# LinePCB_Schematic_ETCautoPrikratki.net
KiCad netlist of a schematic drawn in EasyEDA
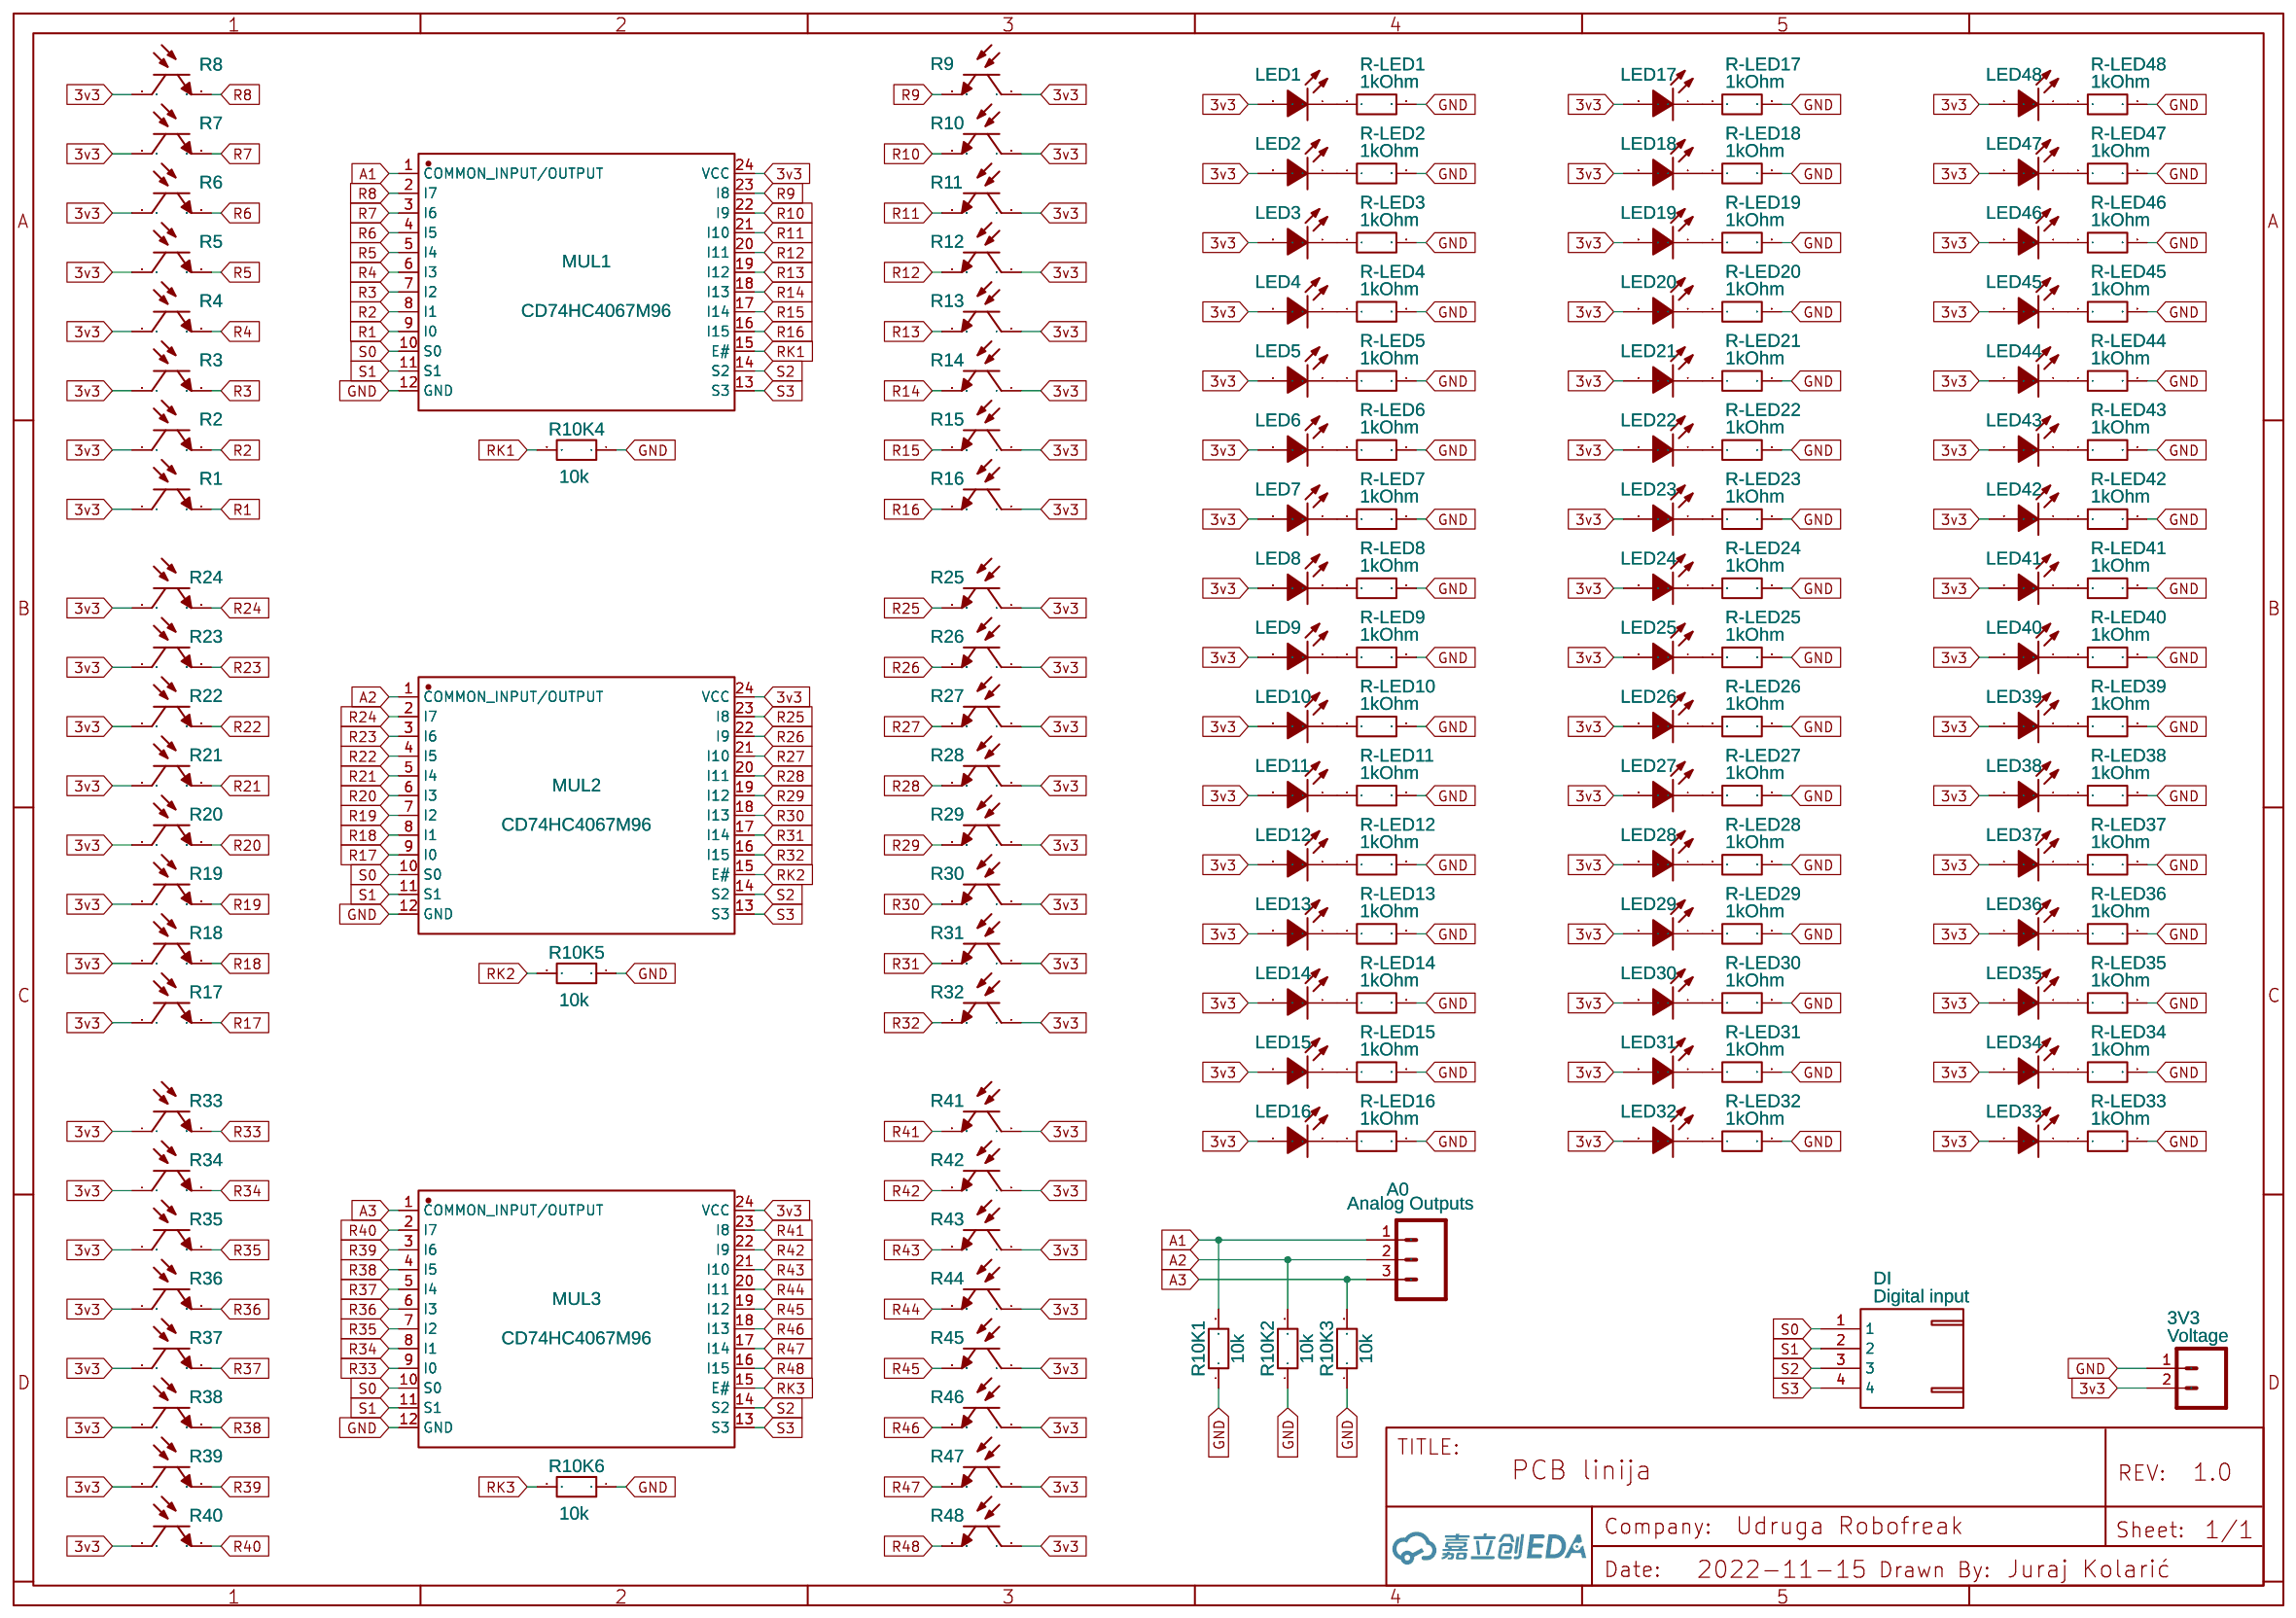
[diagram p0: schematic sheet]

(export (version "E")
  (design (tool "Eeschema 10.0.6"))
  (components
    (comp (ref "3V3") (value "Voltage") (libsource (lib "") (part "JST-XH-1X02-2.50MM-THM JS")))
    (comp (ref "A0") (value "Analog Outputs") (libsource (lib "") (part "JST-XH-1X03-2.50MM-THM JS")))
    (comp (ref "DI") (value "Digital input") (libsource (lib "") (part "JST-XH-4-Pin")))
    (comp (ref "LED1")
      (value "3528 Red LED")
      (fields (field (name "Manufacturer Part") "XL-3528SURC") (field (name "Manufacturer") "XINGLIGHT(成兴光)"))
      (libsource (lib "") (part "3528 Red LED"))
    )
    (comp (ref "LED2")
      (value "3528 Red LED")
      (fields (field (name "Manufacturer Part") "XL-3528SURC") (field (name "Manufacturer") "XINGLIGHT(成兴光)"))
      (libsource (lib "") (part "3528 Red LED"))
    )
    (comp (ref "LED3")
      (value "3528 Red LED")
      (fields (field (name "Manufacturer Part") "XL-3528SURC") (field (name "Manufacturer") "XINGLIGHT(成兴光)"))
      (libsource (lib "") (part "3528 Red LED"))
    )
    (comp (ref "LED4")
      (value "3528 Red LED")
      (fields (field (name "Manufacturer Part") "XL-3528SURC") (field (name "Manufacturer") "XINGLIGHT(成兴光)"))
      (libsource (lib "") (part "3528 Red LED"))
    )
    (comp (ref "LED5")
      (value "3528 Red LED")
      (fields (field (name "Manufacturer Part") "XL-3528SURC") (field (name "Manufacturer") "XINGLIGHT(成兴光)"))
      (libsource (lib "") (part "3528 Red LED"))
    )
    (comp (ref "LED6")
      (value "3528 Red LED")
      (fields (field (name "Manufacturer Part") "XL-3528SURC") (field (name "Manufacturer") "XINGLIGHT(成兴光)"))
      (libsource (lib "") (part "3528 Red LED"))
    )
    (comp (ref "LED7")
      (value "3528 Red LED")
      (fields (field (name "Manufacturer Part") "XL-3528SURC") (field (name "Manufacturer") "XINGLIGHT(成兴光)"))
      (libsource (lib "") (part "3528 Red LED"))
    )
    (comp (ref "LED8")
      (value "3528 Red LED")
      (fields (field (name "Manufacturer Part") "XL-3528SURC") (field (name "Manufacturer") "XINGLIGHT(成兴光)"))
      (libsource (lib "") (part "3528 Red LED"))
    )
    (comp (ref "LED9")
      (value "3528 Red LED")
      (fields (field (name "Manufacturer Part") "XL-3528SURC") (field (name "Manufacturer") "XINGLIGHT(成兴光)"))
      (libsource (lib "") (part "3528 Red LED"))
    )
    (comp (ref "LED10")
      (value "3528 Red LED")
      (fields (field (name "Manufacturer Part") "XL-3528SURC") (field (name "Manufacturer") "XINGLIGHT(成兴光)"))
      (libsource (lib "") (part "3528 Red LED"))
    )
    (comp (ref "LED11")
      (value "3528 Red LED")
      (fields (field (name "Manufacturer Part") "XL-3528SURC") (field (name "Manufacturer") "XINGLIGHT(成兴光)"))
      (libsource (lib "") (part "3528 Red LED"))
    )
    (comp (ref "LED12")
      (value "3528 Red LED")
      (fields (field (name "Manufacturer Part") "XL-3528SURC") (field (name "Manufacturer") "XINGLIGHT(成兴光)"))
      (libsource (lib "") (part "3528 Red LED"))
    )
    (comp (ref "LED13")
      (value "3528 Red LED")
      (fields (field (name "Manufacturer Part") "XL-3528SURC") (field (name "Manufacturer") "XINGLIGHT(成兴光)"))
      (libsource (lib "") (part "3528 Red LED"))
    )
    (comp (ref "LED14")
      (value "3528 Red LED")
      (fields (field (name "Manufacturer Part") "XL-3528SURC") (field (name "Manufacturer") "XINGLIGHT(成兴光)"))
      (libsource (lib "") (part "3528 Red LED"))
    )
    (comp (ref "LED15")
      (value "3528 Red LED")
      (fields (field (name "Manufacturer Part") "XL-3528SURC") (field (name "Manufacturer") "XINGLIGHT(成兴光)"))
      (libsource (lib "") (part "3528 Red LED"))
    )
    (comp (ref "LED16")
      (value "3528 Red LED")
      (fields (field (name "Manufacturer Part") "XL-3528SURC") (field (name "Manufacturer") "XINGLIGHT(成兴光)"))
      (libsource (lib "") (part "3528 Red LED"))
    )
    (comp (ref "LED17")
      (value "3528 Red LED")
      (fields (field (name "Manufacturer Part") "XL-3528SURC") (field (name "Manufacturer") "XINGLIGHT(成兴光)"))
      (libsource (lib "") (part "3528 Red LED"))
    )
    (comp (ref "LED18")
      (value "3528 Red LED")
      (fields (field (name "Manufacturer Part") "XL-3528SURC") (field (name "Manufacturer") "XINGLIGHT(成兴光)"))
      (libsource (lib "") (part "3528 Red LED"))
    )
    (comp (ref "LED19")
      (value "3528 Red LED")
      (fields (field (name "Manufacturer Part") "XL-3528SURC") (field (name "Manufacturer") "XINGLIGHT(成兴光)"))
      (libsource (lib "") (part "3528 Red LED"))
    )
    (comp (ref "LED20")
      (value "3528 Red LED")
      (fields (field (name "Manufacturer Part") "XL-3528SURC") (field (name "Manufacturer") "XINGLIGHT(成兴光)"))
      (libsource (lib "") (part "3528 Red LED"))
    )
    (comp (ref "LED21")
      (value "3528 Red LED")
      (fields (field (name "Manufacturer Part") "XL-3528SURC") (field (name "Manufacturer") "XINGLIGHT(成兴光)"))
      (libsource (lib "") (part "3528 Red LED"))
    )
    (comp (ref "LED22")
      (value "3528 Red LED")
      (fields (field (name "Manufacturer Part") "XL-3528SURC") (field (name "Manufacturer") "XINGLIGHT(成兴光)"))
      (libsource (lib "") (part "3528 Red LED"))
    )
    (comp (ref "LED23")
      (value "3528 Red LED")
      (fields (field (name "Manufacturer Part") "XL-3528SURC") (field (name "Manufacturer") "XINGLIGHT(成兴光)"))
      (libsource (lib "") (part "3528 Red LED"))
    )
    (comp (ref "LED24")
      (value "3528 Red LED")
      (fields (field (name "Manufacturer Part") "XL-3528SURC") (field (name "Manufacturer") "XINGLIGHT(成兴光)"))
      (libsource (lib "") (part "3528 Red LED"))
    )
    (comp (ref "LED25")
      (value "3528 Red LED")
      (fields (field (name "Manufacturer Part") "XL-3528SURC") (field (name "Manufacturer") "XINGLIGHT(成兴光)"))
      (libsource (lib "") (part "3528 Red LED"))
    )
    (comp (ref "LED26")
      (value "3528 Red LED")
      (fields (field (name "Manufacturer Part") "XL-3528SURC") (field (name "Manufacturer") "XINGLIGHT(成兴光)"))
      (libsource (lib "") (part "3528 Red LED"))
    )
    (comp (ref "LED27")
      (value "3528 Red LED")
      (fields (field (name "Manufacturer Part") "XL-3528SURC") (field (name "Manufacturer") "XINGLIGHT(成兴光)"))
      (libsource (lib "") (part "3528 Red LED"))
    )
    (comp (ref "LED28")
      (value "3528 Red LED")
      (fields (field (name "Manufacturer Part") "XL-3528SURC") (field (name "Manufacturer") "XINGLIGHT(成兴光)"))
      (libsource (lib "") (part "3528 Red LED"))
    )
    (comp (ref "LED29")
      (value "3528 Red LED")
      (fields (field (name "Manufacturer Part") "XL-3528SURC") (field (name "Manufacturer") "XINGLIGHT(成兴光)"))
      (libsource (lib "") (part "3528 Red LED"))
    )
    (comp (ref "LED30")
      (value "3528 Red LED")
      (fields (field (name "Manufacturer Part") "XL-3528SURC") (field (name "Manufacturer") "XINGLIGHT(成兴光)"))
      (libsource (lib "") (part "3528 Red LED"))
    )
    (comp (ref "LED31")
      (value "3528 Red LED")
      (fields (field (name "Manufacturer Part") "XL-3528SURC") (field (name "Manufacturer") "XINGLIGHT(成兴光)"))
      (libsource (lib "") (part "3528 Red LED"))
    )
    (comp (ref "LED32")
      (value "3528 Red LED")
      (fields (field (name "Manufacturer Part") "XL-3528SURC") (field (name "Manufacturer") "XINGLIGHT(成兴光)"))
      (libsource (lib "") (part "3528 Red LED"))
    )
    (comp (ref "LED33")
      (value "3528 Red LED")
      (fields (field (name "Manufacturer Part") "XL-3528SURC") (field (name "Manufacturer") "XINGLIGHT(成兴光)"))
      (libsource (lib "") (part "3528 Red LED"))
    )
    (comp (ref "LED34")
      (value "3528 Red LED")
      (fields (field (name "Manufacturer Part") "XL-3528SURC") (field (name "Manufacturer") "XINGLIGHT(成兴光)"))
      (libsource (lib "") (part "3528 Red LED"))
    )
    (comp (ref "LED35")
      (value "3528 Red LED")
      (fields (field (name "Manufacturer Part") "XL-3528SURC") (field (name "Manufacturer") "XINGLIGHT(成兴光)"))
      (libsource (lib "") (part "3528 Red LED"))
    )
    (comp (ref "LED36")
      (value "3528 Red LED")
      (fields (field (name "Manufacturer Part") "XL-3528SURC") (field (name "Manufacturer") "XINGLIGHT(成兴光)"))
      (libsource (lib "") (part "3528 Red LED"))
    )
    (comp (ref "LED37")
      (value "3528 Red LED")
      (fields (field (name "Manufacturer Part") "XL-3528SURC") (field (name "Manufacturer") "XINGLIGHT(成兴光)"))
      (libsource (lib "") (part "3528 Red LED"))
    )
    (comp (ref "LED38")
      (value "3528 Red LED")
      (fields (field (name "Manufacturer Part") "XL-3528SURC") (field (name "Manufacturer") "XINGLIGHT(成兴光)"))
      (libsource (lib "") (part "3528 Red LED"))
    )
    (comp (ref "LED39")
      (value "3528 Red LED")
      (fields (field (name "Manufacturer Part") "XL-3528SURC") (field (name "Manufacturer") "XINGLIGHT(成兴光)"))
      (libsource (lib "") (part "3528 Red LED"))
    )
    (comp (ref "LED40")
      (value "3528 Red LED")
      (fields (field (name "Manufacturer Part") "XL-3528SURC") (field (name "Manufacturer") "XINGLIGHT(成兴光)"))
      (libsource (lib "") (part "3528 Red LED"))
    )
    (comp (ref "LED41")
      (value "3528 Red LED")
      (fields (field (name "Manufacturer Part") "XL-3528SURC") (field (name "Manufacturer") "XINGLIGHT(成兴光)"))
      (libsource (lib "") (part "3528 Red LED"))
    )
    (comp (ref "LED42")
      (value "3528 Red LED")
      (fields (field (name "Manufacturer Part") "XL-3528SURC") (field (name "Manufacturer") "XINGLIGHT(成兴光)"))
      (libsource (lib "") (part "3528 Red LED"))
    )
    (comp (ref "LED43")
      (value "3528 Red LED")
      (fields (field (name "Manufacturer Part") "XL-3528SURC") (field (name "Manufacturer") "XINGLIGHT(成兴光)"))
      (libsource (lib "") (part "3528 Red LED"))
    )
    (comp (ref "LED44")
      (value "3528 Red LED")
      (fields (field (name "Manufacturer Part") "XL-3528SURC") (field (name "Manufacturer") "XINGLIGHT(成兴光)"))
      (libsource (lib "") (part "3528 Red LED"))
    )
    (comp (ref "LED45")
      (value "3528 Red LED")
      (fields (field (name "Manufacturer Part") "XL-3528SURC") (field (name "Manufacturer") "XINGLIGHT(成兴光)"))
      (libsource (lib "") (part "3528 Red LED"))
    )
    (comp (ref "LED46")
      (value "3528 Red LED")
      (fields (field (name "Manufacturer Part") "XL-3528SURC") (field (name "Manufacturer") "XINGLIGHT(成兴光)"))
      (libsource (lib "") (part "3528 Red LED"))
    )
    (comp (ref "LED47")
      (value "3528 Red LED")
      (fields (field (name "Manufacturer Part") "XL-3528SURC") (field (name "Manufacturer") "XINGLIGHT(成兴光)"))
      (libsource (lib "") (part "3528 Red LED"))
    )
    (comp (ref "LED48")
      (value "3528 Red LED")
      (fields (field (name "Manufacturer Part") "XL-3528SURC") (field (name "Manufacturer") "XINGLIGHT(成兴光)"))
      (libsource (lib "") (part "3528 Red LED"))
    )
    (comp (ref "MUL1")
      (value "CD74HC4067M96")
      (fields (field (name "Manufacturer") "TI(德州仪器)"))
      (libsource (lib "") (part "CD74HC4067M96"))
    )
    (comp (ref "MUL2")
      (value "CD74HC4067M96")
      (fields (field (name "Manufacturer") "TI(德州仪器)"))
      (libsource (lib "") (part "CD74HC4067M96"))
    )
    (comp (ref "MUL3")
      (value "CD74HC4067M96")
      (fields (field (name "Manufacturer") "TI(德州仪器)"))
      (libsource (lib "") (part "CD74HC4067M96"))
    )
    (comp (ref "R-LED1") (value "1kOhm") (libsource (lib "") (part "R_AXIAL-0.3_EU")))
    (comp (ref "R-LED2") (value "1kOhm") (libsource (lib "") (part "R_AXIAL-0.3_EU")))
    (comp (ref "R-LED3") (value "1kOhm") (libsource (lib "") (part "R_AXIAL-0.3_EU")))
    (comp (ref "R-LED4") (value "1kOhm") (libsource (lib "") (part "R_AXIAL-0.3_EU")))
    (comp (ref "R-LED5") (value "1kOhm") (libsource (lib "") (part "R_AXIAL-0.3_EU")))
    (comp (ref "R-LED6") (value "1kOhm") (libsource (lib "") (part "R_AXIAL-0.3_EU")))
    (comp (ref "R-LED7") (value "1kOhm") (libsource (lib "") (part "R_AXIAL-0.3_EU")))
    (comp (ref "R-LED8") (value "1kOhm") (libsource (lib "") (part "R_AXIAL-0.3_EU")))
    (comp (ref "R-LED9") (value "1kOhm") (libsource (lib "") (part "R_AXIAL-0.3_EU")))
    (comp (ref "R-LED10") (value "1kOhm") (libsource (lib "") (part "R_AXIAL-0.3_EU")))
    (comp (ref "R-LED11") (value "1kOhm") (libsource (lib "") (part "R_AXIAL-0.3_EU")))
    (comp (ref "R-LED12") (value "1kOhm") (libsource (lib "") (part "R_AXIAL-0.3_EU")))
    (comp (ref "R-LED13") (value "1kOhm") (libsource (lib "") (part "R_AXIAL-0.3_EU")))
    (comp (ref "R-LED14") (value "1kOhm") (libsource (lib "") (part "R_AXIAL-0.3_EU")))
    (comp (ref "R-LED15") (value "1kOhm") (libsource (lib "") (part "R_AXIAL-0.3_EU")))
    (comp (ref "R-LED16") (value "1kOhm") (libsource (lib "") (part "R_AXIAL-0.3_EU")))
    (comp (ref "R-LED17") (value "1kOhm") (libsource (lib "") (part "R_AXIAL-0.3_EU")))
    (comp (ref "R-LED18") (value "1kOhm") (libsource (lib "") (part "R_AXIAL-0.3_EU")))
    (comp (ref "R-LED19") (value "1kOhm") (libsource (lib "") (part "R_AXIAL-0.3_EU")))
    (comp (ref "R-LED20") (value "1kOhm") (libsource (lib "") (part "R_AXIAL-0.3_EU")))
    (comp (ref "R-LED21") (value "1kOhm") (libsource (lib "") (part "R_AXIAL-0.3_EU")))
    (comp (ref "R-LED22") (value "1kOhm") (libsource (lib "") (part "R_AXIAL-0.3_EU")))
    (comp (ref "R-LED23") (value "1kOhm") (libsource (lib "") (part "R_AXIAL-0.3_EU")))
    (comp (ref "R-LED24") (value "1kOhm") (libsource (lib "") (part "R_AXIAL-0.3_EU")))
    (comp (ref "R-LED25") (value "1kOhm") (libsource (lib "") (part "R_AXIAL-0.3_EU")))
    (comp (ref "R-LED26") (value "1kOhm") (libsource (lib "") (part "R_AXIAL-0.3_EU")))
    (comp (ref "R-LED27") (value "1kOhm") (libsource (lib "") (part "R_AXIAL-0.3_EU")))
    (comp (ref "R-LED28") (value "1kOhm") (libsource (lib "") (part "R_AXIAL-0.3_EU")))
    (comp (ref "R-LED29") (value "1kOhm") (libsource (lib "") (part "R_AXIAL-0.3_EU")))
    (comp (ref "R-LED30") (value "1kOhm") (libsource (lib "") (part "R_AXIAL-0.3_EU")))
    (comp (ref "R-LED31") (value "1kOhm") (libsource (lib "") (part "R_AXIAL-0.3_EU")))
    (comp (ref "R-LED32") (value "1kOhm") (libsource (lib "") (part "R_AXIAL-0.3_EU")))
    (comp (ref "R-LED33") (value "1kOhm") (libsource (lib "") (part "R_AXIAL-0.3_EU")))
    (comp (ref "R-LED34") (value "1kOhm") (libsource (lib "") (part "R_AXIAL-0.3_EU")))
    (comp (ref "R-LED35") (value "1kOhm") (libsource (lib "") (part "R_AXIAL-0.3_EU")))
    (comp (ref "R-LED36") (value "1kOhm") (libsource (lib "") (part "R_AXIAL-0.3_EU")))
    (comp (ref "R-LED37") (value "1kOhm") (libsource (lib "") (part "R_AXIAL-0.3_EU")))
    (comp (ref "R-LED38") (value "1kOhm") (libsource (lib "") (part "R_AXIAL-0.3_EU")))
    (comp (ref "R-LED39") (value "1kOhm") (libsource (lib "") (part "R_AXIAL-0.3_EU")))
    (comp (ref "R-LED40") (value "1kOhm") (libsource (lib "") (part "R_AXIAL-0.3_EU")))
    (comp (ref "R-LED41") (value "1kOhm") (libsource (lib "") (part "R_AXIAL-0.3_EU")))
    (comp (ref "R-LED42") (value "1kOhm") (libsource (lib "") (part "R_AXIAL-0.3_EU")))
    (comp (ref "R-LED43") (value "1kOhm") (libsource (lib "") (part "R_AXIAL-0.3_EU")))
    (comp (ref "R-LED44") (value "1kOhm") (libsource (lib "") (part "R_AXIAL-0.3_EU")))
    (comp (ref "R-LED45") (value "1kOhm") (libsource (lib "") (part "R_AXIAL-0.3_EU")))
    (comp (ref "R-LED46") (value "1kOhm") (libsource (lib "") (part "R_AXIAL-0.3_EU")))
    (comp (ref "R-LED47") (value "1kOhm") (libsource (lib "") (part "R_AXIAL-0.3_EU")))
    (comp (ref "R-LED48") (value "1kOhm") (libsource (lib "") (part "R_AXIAL-0.3_EU")))
    (comp (ref "R1")
      (value "ALS-PT19-315C/L177/TR8")
      (fields (field (name "Manufacturer") "EVERLIGHT"))
      (libsource (lib "") (part "ALS-PT19-315C/L177/TR8"))
    )
    (comp (ref "R2")
      (value "ALS-PT19-315C/L177/TR8")
      (fields (field (name "Manufacturer") "EVERLIGHT"))
      (libsource (lib "") (part "ALS-PT19-315C/L177/TR8"))
    )
    (comp (ref "R3")
      (value "ALS-PT19-315C/L177/TR8")
      (fields (field (name "Manufacturer") "EVERLIGHT"))
      (libsource (lib "") (part "ALS-PT19-315C/L177/TR8"))
    )
    (comp (ref "R4")
      (value "ALS-PT19-315C/L177/TR8")
      (fields (field (name "Manufacturer") "EVERLIGHT"))
      (libsource (lib "") (part "ALS-PT19-315C/L177/TR8"))
    )
    (comp (ref "R5")
      (value "ALS-PT19-315C/L177/TR8")
      (fields (field (name "Manufacturer") "EVERLIGHT"))
      (libsource (lib "") (part "ALS-PT19-315C/L177/TR8"))
    )
    (comp (ref "R6")
      (value "ALS-PT19-315C/L177/TR8")
      (fields (field (name "Manufacturer") "EVERLIGHT"))
      (libsource (lib "") (part "ALS-PT19-315C/L177/TR8"))
    )
    (comp (ref "R7")
      (value "ALS-PT19-315C/L177/TR8")
      (fields (field (name "Manufacturer") "EVERLIGHT"))
      (libsource (lib "") (part "ALS-PT19-315C/L177/TR8"))
    )
    (comp (ref "R8")
      (value "ALS-PT19-315C/L177/TR8")
      (fields (field (name "Manufacturer") "EVERLIGHT"))
      (libsource (lib "") (part "ALS-PT19-315C/L177/TR8"))
    )
    (comp (ref "R9")
      (value "ALS-PT19-315C/L177/TR8")
      (fields (field (name "Manufacturer") "EVERLIGHT"))
      (libsource (lib "") (part "ALS-PT19-315C/L177/TR8_1"))
    )
    (comp (ref "R10")
      (value "ALS-PT19-315C/L177/TR8")
      (fields (field (name "Manufacturer") "EVERLIGHT"))
      (libsource (lib "") (part "ALS-PT19-315C/L177/TR8_1"))
    )
    (comp (ref "R10K1") (value "10k") (libsource (lib "") (part "R_AXIAL-0.3_EU_1")))
    (comp (ref "R10K2") (value "10k") (libsource (lib "") (part "R_AXIAL-0.3_EU_1")))
    (comp (ref "R10K3") (value "10k") (libsource (lib "") (part "R_AXIAL-0.3_EU_1")))
    (comp (ref "R10K4") (value "10k") (libsource (lib "") (part "R_AXIAL-0.3_EU_2")))
    (comp (ref "R10K5") (value "10k") (libsource (lib "") (part "R_AXIAL-0.3_EU_2")))
    (comp (ref "R10K6") (value "10k") (libsource (lib "") (part "R_AXIAL-0.3_EU_2")))
    (comp (ref "R11")
      (value "ALS-PT19-315C/L177/TR8")
      (fields (field (name "Manufacturer") "EVERLIGHT"))
      (libsource (lib "") (part "ALS-PT19-315C/L177/TR8_1"))
    )
    (comp (ref "R12")
      (value "ALS-PT19-315C/L177/TR8")
      (fields (field (name "Manufacturer") "EVERLIGHT"))
      (libsource (lib "") (part "ALS-PT19-315C/L177/TR8_1"))
    )
    (comp (ref "R13")
      (value "ALS-PT19-315C/L177/TR8")
      (fields (field (name "Manufacturer") "EVERLIGHT"))
      (libsource (lib "") (part "ALS-PT19-315C/L177/TR8_1"))
    )
    (comp (ref "R14")
      (value "ALS-PT19-315C/L177/TR8")
      (fields (field (name "Manufacturer") "EVERLIGHT"))
      (libsource (lib "") (part "ALS-PT19-315C/L177/TR8_1"))
    )
    (comp (ref "R15")
      (value "ALS-PT19-315C/L177/TR8")
      (fields (field (name "Manufacturer") "EVERLIGHT"))
      (libsource (lib "") (part "ALS-PT19-315C/L177/TR8_1"))
    )
    (comp (ref "R16")
      (value "ALS-PT19-315C/L177/TR8")
      (fields (field (name "Manufacturer") "EVERLIGHT"))
      (libsource (lib "") (part "ALS-PT19-315C/L177/TR8_1"))
    )
    (comp (ref "R17")
      (value "ALS-PT19-315C/L177/TR8")
      (fields (field (name "Manufacturer") "EVERLIGHT"))
      (libsource (lib "") (part "ALS-PT19-315C/L177/TR8"))
    )
    (comp (ref "R18")
      (value "ALS-PT19-315C/L177/TR8")
      (fields (field (name "Manufacturer") "EVERLIGHT"))
      (libsource (lib "") (part "ALS-PT19-315C/L177/TR8"))
    )
    (comp (ref "R19")
      (value "ALS-PT19-315C/L177/TR8")
      (fields (field (name "Manufacturer") "EVERLIGHT"))
      (libsource (lib "") (part "ALS-PT19-315C/L177/TR8"))
    )
    (comp (ref "R20")
      (value "ALS-PT19-315C/L177/TR8")
      (fields (field (name "Manufacturer") "EVERLIGHT"))
      (libsource (lib "") (part "ALS-PT19-315C/L177/TR8"))
    )
    (comp (ref "R21")
      (value "ALS-PT19-315C/L177/TR8")
      (fields (field (name "Manufacturer") "EVERLIGHT"))
      (libsource (lib "") (part "ALS-PT19-315C/L177/TR8"))
    )
    (comp (ref "R22")
      (value "ALS-PT19-315C/L177/TR8")
      (fields (field (name "Manufacturer") "EVERLIGHT"))
      (libsource (lib "") (part "ALS-PT19-315C/L177/TR8"))
    )
    (comp (ref "R23")
      (value "ALS-PT19-315C/L177/TR8")
      (fields (field (name "Manufacturer") "EVERLIGHT"))
      (libsource (lib "") (part "ALS-PT19-315C/L177/TR8"))
    )
    (comp (ref "R24")
      (value "ALS-PT19-315C/L177/TR8")
      (fields (field (name "Manufacturer") "EVERLIGHT"))
      (libsource (lib "") (part "ALS-PT19-315C/L177/TR8"))
    )
    (comp (ref "R25")
      (value "ALS-PT19-315C/L177/TR8")
      (fields (field (name "Manufacturer") "EVERLIGHT"))
      (libsource (lib "") (part "ALS-PT19-315C/L177/TR8_1"))
    )
    (comp (ref "R26")
      (value "ALS-PT19-315C/L177/TR8")
      (fields (field (name "Manufacturer") "EVERLIGHT"))
      (libsource (lib "") (part "ALS-PT19-315C/L177/TR8_1"))
    )
    (comp (ref "R27")
      (value "ALS-PT19-315C/L177/TR8")
      (fields (field (name "Manufacturer") "EVERLIGHT"))
      (libsource (lib "") (part "ALS-PT19-315C/L177/TR8_1"))
    )
    (comp (ref "R28")
      (value "ALS-PT19-315C/L177/TR8")
      (fields (field (name "Manufacturer") "EVERLIGHT"))
      (libsource (lib "") (part "ALS-PT19-315C/L177/TR8_1"))
    )
    (comp (ref "R29")
      (value "ALS-PT19-315C/L177/TR8")
      (fields (field (name "Manufacturer") "EVERLIGHT"))
      (libsource (lib "") (part "ALS-PT19-315C/L177/TR8_1"))
    )
    (comp (ref "R30")
      (value "ALS-PT19-315C/L177/TR8")
      (fields (field (name "Manufacturer") "EVERLIGHT"))
      (libsource (lib "") (part "ALS-PT19-315C/L177/TR8_1"))
    )
    (comp (ref "R31")
      (value "ALS-PT19-315C/L177/TR8")
      (fields (field (name "Manufacturer") "EVERLIGHT"))
      (libsource (lib "") (part "ALS-PT19-315C/L177/TR8_1"))
    )
    (comp (ref "R32")
      (value "ALS-PT19-315C/L177/TR8")
      (fields (field (name "Manufacturer") "EVERLIGHT"))
      (libsource (lib "") (part "ALS-PT19-315C/L177/TR8_1"))
    )
    (comp (ref "R33")
      (value "ALS-PT19-315C/L177/TR8")
      (fields (field (name "Manufacturer") "EVERLIGHT"))
      (libsource (lib "") (part "ALS-PT19-315C/L177/TR8"))
    )
    (comp (ref "R34")
      (value "ALS-PT19-315C/L177/TR8")
      (fields (field (name "Manufacturer") "EVERLIGHT"))
      (libsource (lib "") (part "ALS-PT19-315C/L177/TR8"))
    )
    (comp (ref "R35")
      (value "ALS-PT19-315C/L177/TR8")
      (fields (field (name "Manufacturer") "EVERLIGHT"))
      (libsource (lib "") (part "ALS-PT19-315C/L177/TR8"))
    )
    (comp (ref "R36")
      (value "ALS-PT19-315C/L177/TR8")
      (fields (field (name "Manufacturer") "EVERLIGHT"))
      (libsource (lib "") (part "ALS-PT19-315C/L177/TR8"))
    )
    (comp (ref "R37")
      (value "ALS-PT19-315C/L177/TR8")
      (fields (field (name "Manufacturer") "EVERLIGHT"))
      (libsource (lib "") (part "ALS-PT19-315C/L177/TR8"))
    )
    (comp (ref "R38")
      (value "ALS-PT19-315C/L177/TR8")
      (fields (field (name "Manufacturer") "EVERLIGHT"))
      (libsource (lib "") (part "ALS-PT19-315C/L177/TR8"))
    )
    (comp (ref "R39")
      (value "ALS-PT19-315C/L177/TR8")
      (fields (field (name "Manufacturer") "EVERLIGHT"))
      (libsource (lib "") (part "ALS-PT19-315C/L177/TR8"))
    )
    (comp (ref "R40")
      (value "ALS-PT19-315C/L177/TR8")
      (fields (field (name "Manufacturer") "EVERLIGHT"))
      (libsource (lib "") (part "ALS-PT19-315C/L177/TR8"))
    )
    (comp (ref "R41")
      (value "ALS-PT19-315C/L177/TR8")
      (fields (field (name "Manufacturer") "EVERLIGHT"))
      (libsource (lib "") (part "ALS-PT19-315C/L177/TR8_1"))
    )
    (comp (ref "R42")
      (value "ALS-PT19-315C/L177/TR8")
      (fields (field (name "Manufacturer") "EVERLIGHT"))
      (libsource (lib "") (part "ALS-PT19-315C/L177/TR8_1"))
    )
    (comp (ref "R43")
      (value "ALS-PT19-315C/L177/TR8")
      (fields (field (name "Manufacturer") "EVERLIGHT"))
      (libsource (lib "") (part "ALS-PT19-315C/L177/TR8_1"))
    )
    (comp (ref "R44")
      (value "ALS-PT19-315C/L177/TR8")
      (fields (field (name "Manufacturer") "EVERLIGHT"))
      (libsource (lib "") (part "ALS-PT19-315C/L177/TR8_1"))
    )
    (comp (ref "R45")
      (value "ALS-PT19-315C/L177/TR8")
      (fields (field (name "Manufacturer") "EVERLIGHT"))
      (libsource (lib "") (part "ALS-PT19-315C/L177/TR8_1"))
    )
    (comp (ref "R46")
      (value "ALS-PT19-315C/L177/TR8")
      (fields (field (name "Manufacturer") "EVERLIGHT"))
      (libsource (lib "") (part "ALS-PT19-315C/L177/TR8_1"))
    )
    (comp (ref "R47")
      (value "ALS-PT19-315C/L177/TR8")
      (fields (field (name "Manufacturer") "EVERLIGHT"))
      (libsource (lib "") (part "ALS-PT19-315C/L177/TR8_1"))
    )
    (comp (ref "R48")
      (value "ALS-PT19-315C/L177/TR8")
      (fields (field (name "Manufacturer") "EVERLIGHT"))
      (libsource (lib "") (part "ALS-PT19-315C/L177/TR8_1"))
    )
  )
  (nets
    (net (code "1") (name "3v3") (class "Default")
      (node (ref "3V3") (pin "2") (pinfunction "2_2") (pintype "unspecified"))
      (node (ref "LED1") (pin "2") (pinfunction "A_2") (pintype "unspecified"))
      (node (ref "LED10") (pin "2") (pinfunction "A_2") (pintype "unspecified"))
      (node (ref "LED11") (pin "2") (pinfunction "A_2") (pintype "unspecified"))
      (node (ref "LED12") (pin "2") (pinfunction "A_2") (pintype "unspecified"))
      (node (ref "LED13") (pin "2") (pinfunction "A_2") (pintype "unspecified"))
      (node (ref "LED14") (pin "2") (pinfunction "A_2") (pintype "unspecified"))
      (node (ref "LED15") (pin "2") (pinfunction "A_2") (pintype "unspecified"))
      (node (ref "LED16") (pin "2") (pinfunction "A_2") (pintype "unspecified"))
      (node (ref "LED17") (pin "2") (pinfunction "A_2") (pintype "unspecified"))
      (node (ref "LED18") (pin "2") (pinfunction "A_2") (pintype "unspecified"))
      (node (ref "LED19") (pin "2") (pinfunction "A_2") (pintype "unspecified"))
      (node (ref "LED2") (pin "2") (pinfunction "A_2") (pintype "unspecified"))
      (node (ref "LED20") (pin "2") (pinfunction "A_2") (pintype "unspecified"))
      (node (ref "LED21") (pin "2") (pinfunction "A_2") (pintype "unspecified"))
      (node (ref "LED22") (pin "2") (pinfunction "A_2") (pintype "unspecified"))
      (node (ref "LED23") (pin "2") (pinfunction "A_2") (pintype "unspecified"))
      (node (ref "LED24") (pin "2") (pinfunction "A_2") (pintype "unspecified"))
      (node (ref "LED25") (pin "2") (pinfunction "A_2") (pintype "unspecified"))
      (node (ref "LED26") (pin "2") (pinfunction "A_2") (pintype "unspecified"))
      (node (ref "LED27") (pin "2") (pinfunction "A_2") (pintype "unspecified"))
      (node (ref "LED28") (pin "2") (pinfunction "A_2") (pintype "unspecified"))
      (node (ref "LED29") (pin "2") (pinfunction "A_2") (pintype "unspecified"))
      (node (ref "LED3") (pin "2") (pinfunction "A_2") (pintype "unspecified"))
      (node (ref "LED30") (pin "2") (pinfunction "A_2") (pintype "unspecified"))
      (node (ref "LED31") (pin "2") (pinfunction "A_2") (pintype "unspecified"))
      (node (ref "LED32") (pin "2") (pinfunction "A_2") (pintype "unspecified"))
      (node (ref "LED33") (pin "2") (pinfunction "A_2") (pintype "unspecified"))
      (node (ref "LED34") (pin "2") (pinfunction "A_2") (pintype "unspecified"))
      (node (ref "LED35") (pin "2") (pinfunction "A_2") (pintype "unspecified"))
      (node (ref "LED36") (pin "2") (pinfunction "A_2") (pintype "unspecified"))
      (node (ref "LED37") (pin "2") (pinfunction "A_2") (pintype "unspecified"))
      (node (ref "LED38") (pin "2") (pinfunction "A_2") (pintype "unspecified"))
      (node (ref "LED39") (pin "2") (pinfunction "A_2") (pintype "unspecified"))
      (node (ref "LED4") (pin "2") (pinfunction "A_2") (pintype "unspecified"))
      (node (ref "LED40") (pin "2") (pinfunction "A_2") (pintype "unspecified"))
      (node (ref "LED41") (pin "2") (pinfunction "A_2") (pintype "unspecified"))
      (node (ref "LED42") (pin "2") (pinfunction "A_2") (pintype "unspecified"))
      (node (ref "LED43") (pin "2") (pinfunction "A_2") (pintype "unspecified"))
      (node (ref "LED44") (pin "2") (pinfunction "A_2") (pintype "unspecified"))
      (node (ref "LED45") (pin "2") (pinfunction "A_2") (pintype "unspecified"))
      (node (ref "LED46") (pin "2") (pinfunction "A_2") (pintype "unspecified"))
      (node (ref "LED47") (pin "2") (pinfunction "A_2") (pintype "unspecified"))
      (node (ref "LED48") (pin "2") (pinfunction "A_2") (pintype "unspecified"))
      (node (ref "LED5") (pin "2") (pinfunction "A_2") (pintype "unspecified"))
      (node (ref "LED6") (pin "2") (pinfunction "A_2") (pintype "unspecified"))
      (node (ref "LED7") (pin "2") (pinfunction "A_2") (pintype "unspecified"))
      (node (ref "LED8") (pin "2") (pinfunction "A_2") (pintype "unspecified"))
      (node (ref "LED9") (pin "2") (pinfunction "A_2") (pintype "unspecified"))
      (node (ref "MUL1") (pin "24") (pinfunction "VCC_24") (pintype "unspecified"))
      (node (ref "MUL2") (pin "24") (pinfunction "VCC_24") (pintype "unspecified"))
      (node (ref "MUL3") (pin "24") (pinfunction "VCC_24") (pintype "unspecified"))
      (node (ref "R1") (pin "1") (pinfunction "1_1") (pintype "input"))
      (node (ref "R10") (pin "1") (pinfunction "1_1") (pintype "input"))
      (node (ref "R11") (pin "1") (pinfunction "1_1") (pintype "input"))
      (node (ref "R12") (pin "1") (pinfunction "1_1") (pintype "input"))
      (node (ref "R13") (pin "1") (pinfunction "1_1") (pintype "input"))
      (node (ref "R14") (pin "1") (pinfunction "1_1") (pintype "input"))
      (node (ref "R15") (pin "1") (pinfunction "1_1") (pintype "input"))
      (node (ref "R16") (pin "1") (pinfunction "1_1") (pintype "input"))
      (node (ref "R17") (pin "1") (pinfunction "1_1") (pintype "input"))
      (node (ref "R18") (pin "1") (pinfunction "1_1") (pintype "input"))
      (node (ref "R19") (pin "1") (pinfunction "1_1") (pintype "input"))
      (node (ref "R2") (pin "1") (pinfunction "1_1") (pintype "input"))
      (node (ref "R20") (pin "1") (pinfunction "1_1") (pintype "input"))
      (node (ref "R21") (pin "1") (pinfunction "1_1") (pintype "input"))
      (node (ref "R22") (pin "1") (pinfunction "1_1") (pintype "input"))
      (node (ref "R23") (pin "1") (pinfunction "1_1") (pintype "input"))
      (node (ref "R24") (pin "1") (pinfunction "1_1") (pintype "input"))
      (node (ref "R25") (pin "1") (pinfunction "1_1") (pintype "input"))
      (node (ref "R26") (pin "1") (pinfunction "1_1") (pintype "input"))
      (node (ref "R27") (pin "1") (pinfunction "1_1") (pintype "input"))
      (node (ref "R28") (pin "1") (pinfunction "1_1") (pintype "input"))
      (node (ref "R29") (pin "1") (pinfunction "1_1") (pintype "input"))
      (node (ref "R3") (pin "1") (pinfunction "1_1") (pintype "input"))
      (node (ref "R30") (pin "1") (pinfunction "1_1") (pintype "input"))
      (node (ref "R31") (pin "1") (pinfunction "1_1") (pintype "input"))
      (node (ref "R32") (pin "1") (pinfunction "1_1") (pintype "input"))
      (node (ref "R33") (pin "1") (pinfunction "1_1") (pintype "input"))
      (node (ref "R34") (pin "1") (pinfunction "1_1") (pintype "input"))
      (node (ref "R35") (pin "1") (pinfunction "1_1") (pintype "input"))
      (node (ref "R36") (pin "1") (pinfunction "1_1") (pintype "input"))
      (node (ref "R37") (pin "1") (pinfunction "1_1") (pintype "input"))
      (node (ref "R38") (pin "1") (pinfunction "1_1") (pintype "input"))
      (node (ref "R39") (pin "1") (pinfunction "1_1") (pintype "input"))
      (node (ref "R4") (pin "1") (pinfunction "1_1") (pintype "input"))
      (node (ref "R40") (pin "1") (pinfunction "1_1") (pintype "input"))
      (node (ref "R41") (pin "1") (pinfunction "1_1") (pintype "input"))
      (node (ref "R42") (pin "1") (pinfunction "1_1") (pintype "input"))
      (node (ref "R43") (pin "1") (pinfunction "1_1") (pintype "input"))
      (node (ref "R44") (pin "1") (pinfunction "1_1") (pintype "input"))
      (node (ref "R45") (pin "1") (pinfunction "1_1") (pintype "input"))
      (node (ref "R46") (pin "1") (pinfunction "1_1") (pintype "input"))
      (node (ref "R47") (pin "1") (pinfunction "1_1") (pintype "input"))
      (node (ref "R48") (pin "1") (pinfunction "1_1") (pintype "input"))
      (node (ref "R5") (pin "1") (pinfunction "1_1") (pintype "input"))
      (node (ref "R6") (pin "1") (pinfunction "1_1") (pintype "input"))
      (node (ref "R7") (pin "1") (pinfunction "1_1") (pintype "input"))
      (node (ref "R8") (pin "1") (pinfunction "1_1") (pintype "input"))
      (node (ref "R9") (pin "1") (pinfunction "1_1") (pintype "input"))
    )
    (net (code "2") (name "A1") (class "Default")
      (node (ref "A0") (pin "1") (pinfunction "1_1") (pintype "unspecified"))
      (node (ref "MUL1") (pin "1") (pinfunction "COMMON_INPUT/OUTPUT_1") (pintype "unspecified"))
      (node (ref "R10K1") (pin "2") (pinfunction "2_2") (pintype "unspecified"))
    )
    (net (code "3") (name "A2") (class "Default")
      (node (ref "A0") (pin "2") (pinfunction "2_2") (pintype "unspecified"))
      (node (ref "MUL2") (pin "1") (pinfunction "COMMON_INPUT/OUTPUT_1") (pintype "unspecified"))
      (node (ref "R10K2") (pin "2") (pinfunction "2_2") (pintype "unspecified"))
    )
    (net (code "4") (name "A3") (class "Default")
      (node (ref "A0") (pin "3") (pinfunction "3_3") (pintype "unspecified"))
      (node (ref "MUL3") (pin "1") (pinfunction "COMMON_INPUT/OUTPUT_1") (pintype "unspecified"))
      (node (ref "R10K3") (pin "2") (pinfunction "2_2") (pintype "unspecified"))
    )
    (net (code "5") (name "GND") (class "Default")
      (node (ref "3V3") (pin "1") (pinfunction "1_1") (pintype "unspecified"))
      (node (ref "MUL1") (pin "12") (pinfunction "GND_12") (pintype "unspecified"))
      (node (ref "MUL2") (pin "12") (pinfunction "GND_12") (pintype "unspecified"))
      (node (ref "MUL3") (pin "12") (pinfunction "GND_12") (pintype "unspecified"))
      (node (ref "R-LED1") (pin "2") (pinfunction "2_2") (pintype "unspecified"))
      (node (ref "R-LED10") (pin "2") (pinfunction "2_2") (pintype "unspecified"))
      (node (ref "R-LED11") (pin "2") (pinfunction "2_2") (pintype "unspecified"))
      (node (ref "R-LED12") (pin "2") (pinfunction "2_2") (pintype "unspecified"))
      (node (ref "R-LED13") (pin "2") (pinfunction "2_2") (pintype "unspecified"))
      (node (ref "R-LED14") (pin "2") (pinfunction "2_2") (pintype "unspecified"))
      (node (ref "R-LED15") (pin "2") (pinfunction "2_2") (pintype "unspecified"))
      (node (ref "R-LED16") (pin "2") (pinfunction "2_2") (pintype "unspecified"))
      (node (ref "R-LED17") (pin "2") (pinfunction "2_2") (pintype "unspecified"))
      (node (ref "R-LED18") (pin "2") (pinfunction "2_2") (pintype "unspecified"))
      (node (ref "R-LED19") (pin "2") (pinfunction "2_2") (pintype "unspecified"))
      (node (ref "R-LED2") (pin "2") (pinfunction "2_2") (pintype "unspecified"))
      (node (ref "R-LED20") (pin "2") (pinfunction "2_2") (pintype "unspecified"))
      (node (ref "R-LED21") (pin "2") (pinfunction "2_2") (pintype "unspecified"))
      (node (ref "R-LED22") (pin "2") (pinfunction "2_2") (pintype "unspecified"))
      (node (ref "R-LED23") (pin "2") (pinfunction "2_2") (pintype "unspecified"))
      (node (ref "R-LED24") (pin "2") (pinfunction "2_2") (pintype "unspecified"))
      (node (ref "R-LED25") (pin "2") (pinfunction "2_2") (pintype "unspecified"))
      (node (ref "R-LED26") (pin "2") (pinfunction "2_2") (pintype "unspecified"))
      (node (ref "R-LED27") (pin "2") (pinfunction "2_2") (pintype "unspecified"))
      (node (ref "R-LED28") (pin "2") (pinfunction "2_2") (pintype "unspecified"))
      (node (ref "R-LED29") (pin "2") (pinfunction "2_2") (pintype "unspecified"))
      (node (ref "R-LED3") (pin "2") (pinfunction "2_2") (pintype "unspecified"))
      (node (ref "R-LED30") (pin "2") (pinfunction "2_2") (pintype "unspecified"))
      (node (ref "R-LED31") (pin "2") (pinfunction "2_2") (pintype "unspecified"))
      (node (ref "R-LED32") (pin "2") (pinfunction "2_2") (pintype "unspecified"))
      (node (ref "R-LED33") (pin "2") (pinfunction "2_2") (pintype "unspecified"))
      (node (ref "R-LED34") (pin "2") (pinfunction "2_2") (pintype "unspecified"))
      (node (ref "R-LED35") (pin "2") (pinfunction "2_2") (pintype "unspecified"))
      (node (ref "R-LED36") (pin "2") (pinfunction "2_2") (pintype "unspecified"))
      (node (ref "R-LED37") (pin "2") (pinfunction "2_2") (pintype "unspecified"))
      (node (ref "R-LED38") (pin "2") (pinfunction "2_2") (pintype "unspecified"))
      (node (ref "R-LED39") (pin "2") (pinfunction "2_2") (pintype "unspecified"))
      (node (ref "R-LED4") (pin "2") (pinfunction "2_2") (pintype "unspecified"))
      (node (ref "R-LED40") (pin "2") (pinfunction "2_2") (pintype "unspecified"))
      (node (ref "R-LED41") (pin "2") (pinfunction "2_2") (pintype "unspecified"))
      (node (ref "R-LED42") (pin "2") (pinfunction "2_2") (pintype "unspecified"))
      (node (ref "R-LED43") (pin "2") (pinfunction "2_2") (pintype "unspecified"))
      (node (ref "R-LED44") (pin "2") (pinfunction "2_2") (pintype "unspecified"))
      (node (ref "R-LED45") (pin "2") (pinfunction "2_2") (pintype "unspecified"))
      (node (ref "R-LED46") (pin "2") (pinfunction "2_2") (pintype "unspecified"))
      (node (ref "R-LED47") (pin "2") (pinfunction "2_2") (pintype "unspecified"))
      (node (ref "R-LED48") (pin "2") (pinfunction "2_2") (pintype "unspecified"))
      (node (ref "R-LED5") (pin "2") (pinfunction "2_2") (pintype "unspecified"))
      (node (ref "R-LED6") (pin "2") (pinfunction "2_2") (pintype "unspecified"))
      (node (ref "R-LED7") (pin "2") (pinfunction "2_2") (pintype "unspecified"))
      (node (ref "R-LED8") (pin "2") (pinfunction "2_2") (pintype "unspecified"))
      (node (ref "R-LED9") (pin "2") (pinfunction "2_2") (pintype "unspecified"))
      (node (ref "R10K1") (pin "1") (pinfunction "1_1") (pintype "unspecified"))
      (node (ref "R10K2") (pin "1") (pinfunction "1_1") (pintype "unspecified"))
      (node (ref "R10K3") (pin "1") (pinfunction "1_1") (pintype "unspecified"))
      (node (ref "R10K4") (pin "1") (pinfunction "1_1") (pintype "unspecified"))
      (node (ref "R10K5") (pin "1") (pinfunction "1_1") (pintype "unspecified"))
      (node (ref "R10K6") (pin "1") (pinfunction "1_1") (pintype "unspecified"))
    )
    (net (code "6") (name "Net-(LED1-K)") (class "Default")
      (node (ref "LED1") (pin "1") (pinfunction "K_1") (pintype "unspecified"))
      (node (ref "R-LED1") (pin "1") (pinfunction "1_1") (pintype "unspecified"))
    )
    (net (code "7") (name "Net-(LED2-K)") (class "Default")
      (node (ref "LED2") (pin "1") (pinfunction "K_1") (pintype "unspecified"))
      (node (ref "R-LED2") (pin "1") (pinfunction "1_1") (pintype "unspecified"))
    )
    (net (code "8") (name "Net-(LED3-K)") (class "Default")
      (node (ref "LED3") (pin "1") (pinfunction "K_1") (pintype "unspecified"))
      (node (ref "R-LED3") (pin "1") (pinfunction "1_1") (pintype "unspecified"))
    )
    (net (code "9") (name "Net-(LED4-K)") (class "Default")
      (node (ref "LED4") (pin "1") (pinfunction "K_1") (pintype "unspecified"))
      (node (ref "R-LED4") (pin "1") (pinfunction "1_1") (pintype "unspecified"))
    )
    (net (code "10") (name "Net-(LED5-K)") (class "Default")
      (node (ref "LED5") (pin "1") (pinfunction "K_1") (pintype "unspecified"))
      (node (ref "R-LED5") (pin "1") (pinfunction "1_1") (pintype "unspecified"))
    )
    (net (code "11") (name "Net-(LED6-K)") (class "Default")
      (node (ref "LED6") (pin "1") (pinfunction "K_1") (pintype "unspecified"))
      (node (ref "R-LED6") (pin "1") (pinfunction "1_1") (pintype "unspecified"))
    )
    (net (code "12") (name "Net-(LED7-K)") (class "Default")
      (node (ref "LED7") (pin "1") (pinfunction "K_1") (pintype "unspecified"))
      (node (ref "R-LED7") (pin "1") (pinfunction "1_1") (pintype "unspecified"))
    )
    (net (code "13") (name "Net-(LED8-K)") (class "Default")
      (node (ref "LED8") (pin "1") (pinfunction "K_1") (pintype "unspecified"))
      (node (ref "R-LED8") (pin "1") (pinfunction "1_1") (pintype "unspecified"))
    )
    (net (code "14") (name "Net-(LED9-K)") (class "Default")
      (node (ref "LED9") (pin "1") (pinfunction "K_1") (pintype "unspecified"))
      (node (ref "R-LED9") (pin "1") (pinfunction "1_1") (pintype "unspecified"))
    )
    (net (code "15") (name "Net-(LED10-K)") (class "Default")
      (node (ref "LED10") (pin "1") (pinfunction "K_1") (pintype "unspecified"))
      (node (ref "R-LED10") (pin "1") (pinfunction "1_1") (pintype "unspecified"))
    )
    (net (code "16") (name "Net-(LED11-K)") (class "Default")
      (node (ref "LED11") (pin "1") (pinfunction "K_1") (pintype "unspecified"))
      (node (ref "R-LED11") (pin "1") (pinfunction "1_1") (pintype "unspecified"))
    )
    (net (code "17") (name "Net-(LED12-K)") (class "Default")
      (node (ref "LED12") (pin "1") (pinfunction "K_1") (pintype "unspecified"))
      (node (ref "R-LED12") (pin "1") (pinfunction "1_1") (pintype "unspecified"))
    )
    (net (code "18") (name "Net-(LED13-K)") (class "Default")
      (node (ref "LED13") (pin "1") (pinfunction "K_1") (pintype "unspecified"))
      (node (ref "R-LED13") (pin "1") (pinfunction "1_1") (pintype "unspecified"))
    )
    (net (code "19") (name "Net-(LED14-K)") (class "Default")
      (node (ref "LED14") (pin "1") (pinfunction "K_1") (pintype "unspecified"))
      (node (ref "R-LED14") (pin "1") (pinfunction "1_1") (pintype "unspecified"))
    )
    (net (code "20") (name "Net-(LED15-K)") (class "Default")
      (node (ref "LED15") (pin "1") (pinfunction "K_1") (pintype "unspecified"))
      (node (ref "R-LED15") (pin "1") (pinfunction "1_1") (pintype "unspecified"))
    )
    (net (code "21") (name "Net-(LED16-K)") (class "Default")
      (node (ref "LED16") (pin "1") (pinfunction "K_1") (pintype "unspecified"))
      (node (ref "R-LED16") (pin "1") (pinfunction "1_1") (pintype "unspecified"))
    )
    (net (code "22") (name "Net-(LED17-K)") (class "Default")
      (node (ref "LED17") (pin "1") (pinfunction "K_1") (pintype "unspecified"))
      (node (ref "R-LED17") (pin "1") (pinfunction "1_1") (pintype "unspecified"))
    )
    (net (code "23") (name "Net-(LED18-K)") (class "Default")
      (node (ref "LED18") (pin "1") (pinfunction "K_1") (pintype "unspecified"))
      (node (ref "R-LED18") (pin "1") (pinfunction "1_1") (pintype "unspecified"))
    )
    (net (code "24") (name "Net-(LED19-K)") (class "Default")
      (node (ref "LED19") (pin "1") (pinfunction "K_1") (pintype "unspecified"))
      (node (ref "R-LED19") (pin "1") (pinfunction "1_1") (pintype "unspecified"))
    )
    (net (code "25") (name "Net-(LED20-K)") (class "Default")
      (node (ref "LED20") (pin "1") (pinfunction "K_1") (pintype "unspecified"))
      (node (ref "R-LED20") (pin "1") (pinfunction "1_1") (pintype "unspecified"))
    )
    (net (code "26") (name "Net-(LED21-K)") (class "Default")
      (node (ref "LED21") (pin "1") (pinfunction "K_1") (pintype "unspecified"))
      (node (ref "R-LED21") (pin "1") (pinfunction "1_1") (pintype "unspecified"))
    )
    (net (code "27") (name "Net-(LED22-K)") (class "Default")
      (node (ref "LED22") (pin "1") (pinfunction "K_1") (pintype "unspecified"))
      (node (ref "R-LED22") (pin "1") (pinfunction "1_1") (pintype "unspecified"))
    )
    (net (code "28") (name "Net-(LED23-K)") (class "Default")
      (node (ref "LED23") (pin "1") (pinfunction "K_1") (pintype "unspecified"))
      (node (ref "R-LED23") (pin "1") (pinfunction "1_1") (pintype "unspecified"))
    )
    (net (code "29") (name "Net-(LED24-K)") (class "Default")
      (node (ref "LED24") (pin "1") (pinfunction "K_1") (pintype "unspecified"))
      (node (ref "R-LED24") (pin "1") (pinfunction "1_1") (pintype "unspecified"))
    )
    (net (code "30") (name "Net-(LED25-K)") (class "Default")
      (node (ref "LED25") (pin "1") (pinfunction "K_1") (pintype "unspecified"))
      (node (ref "R-LED25") (pin "1") (pinfunction "1_1") (pintype "unspecified"))
    )
    (net (code "31") (name "Net-(LED26-K)") (class "Default")
      (node (ref "LED26") (pin "1") (pinfunction "K_1") (pintype "unspecified"))
      (node (ref "R-LED26") (pin "1") (pinfunction "1_1") (pintype "unspecified"))
    )
    (net (code "32") (name "Net-(LED27-K)") (class "Default")
      (node (ref "LED27") (pin "1") (pinfunction "K_1") (pintype "unspecified"))
      (node (ref "R-LED27") (pin "1") (pinfunction "1_1") (pintype "unspecified"))
    )
    (net (code "33") (name "Net-(LED28-K)") (class "Default")
      (node (ref "LED28") (pin "1") (pinfunction "K_1") (pintype "unspecified"))
      (node (ref "R-LED28") (pin "1") (pinfunction "1_1") (pintype "unspecified"))
    )
    (net (code "34") (name "Net-(LED29-K)") (class "Default")
      (node (ref "LED29") (pin "1") (pinfunction "K_1") (pintype "unspecified"))
      (node (ref "R-LED29") (pin "1") (pinfunction "1_1") (pintype "unspecified"))
    )
    (net (code "35") (name "Net-(LED30-K)") (class "Default")
      (node (ref "LED30") (pin "1") (pinfunction "K_1") (pintype "unspecified"))
      (node (ref "R-LED30") (pin "1") (pinfunction "1_1") (pintype "unspecified"))
    )
    (net (code "36") (name "Net-(LED31-K)") (class "Default")
      (node (ref "LED31") (pin "1") (pinfunction "K_1") (pintype "unspecified"))
      (node (ref "R-LED31") (pin "1") (pinfunction "1_1") (pintype "unspecified"))
    )
    (net (code "37") (name "Net-(LED32-K)") (class "Default")
      (node (ref "LED32") (pin "1") (pinfunction "K_1") (pintype "unspecified"))
      (node (ref "R-LED32") (pin "1") (pinfunction "1_1") (pintype "unspecified"))
    )
    (net (code "38") (name "Net-(LED33-K)") (class "Default")
      (node (ref "LED33") (pin "1") (pinfunction "K_1") (pintype "unspecified"))
      (node (ref "R-LED33") (pin "1") (pinfunction "1_1") (pintype "unspecified"))
    )
    (net (code "39") (name "Net-(LED34-K)") (class "Default")
      (node (ref "LED34") (pin "1") (pinfunction "K_1") (pintype "unspecified"))
      (node (ref "R-LED34") (pin "1") (pinfunction "1_1") (pintype "unspecified"))
    )
    (net (code "40") (name "Net-(LED35-K)") (class "Default")
      (node (ref "LED35") (pin "1") (pinfunction "K_1") (pintype "unspecified"))
      (node (ref "R-LED35") (pin "1") (pinfunction "1_1") (pintype "unspecified"))
    )
    (net (code "41") (name "Net-(LED36-K)") (class "Default")
      (node (ref "LED36") (pin "1") (pinfunction "K_1") (pintype "unspecified"))
      (node (ref "R-LED36") (pin "1") (pinfunction "1_1") (pintype "unspecified"))
    )
    (net (code "42") (name "Net-(LED37-K)") (class "Default")
      (node (ref "LED37") (pin "1") (pinfunction "K_1") (pintype "unspecified"))
      (node (ref "R-LED37") (pin "1") (pinfunction "1_1") (pintype "unspecified"))
    )
    (net (code "43") (name "Net-(LED38-K)") (class "Default")
      (node (ref "LED38") (pin "1") (pinfunction "K_1") (pintype "unspecified"))
      (node (ref "R-LED38") (pin "1") (pinfunction "1_1") (pintype "unspecified"))
    )
    (net (code "44") (name "Net-(LED39-K)") (class "Default")
      (node (ref "LED39") (pin "1") (pinfunction "K_1") (pintype "unspecified"))
      (node (ref "R-LED39") (pin "1") (pinfunction "1_1") (pintype "unspecified"))
    )
    (net (code "45") (name "Net-(LED40-K)") (class "Default")
      (node (ref "LED40") (pin "1") (pinfunction "K_1") (pintype "unspecified"))
      (node (ref "R-LED40") (pin "1") (pinfunction "1_1") (pintype "unspecified"))
    )
    (net (code "46") (name "Net-(LED41-K)") (class "Default")
      (node (ref "LED41") (pin "1") (pinfunction "K_1") (pintype "unspecified"))
      (node (ref "R-LED41") (pin "1") (pinfunction "1_1") (pintype "unspecified"))
    )
    (net (code "47") (name "Net-(LED42-K)") (class "Default")
      (node (ref "LED42") (pin "1") (pinfunction "K_1") (pintype "unspecified"))
      (node (ref "R-LED42") (pin "1") (pinfunction "1_1") (pintype "unspecified"))
    )
    (net (code "48") (name "Net-(LED43-K)") (class "Default")
      (node (ref "LED43") (pin "1") (pinfunction "K_1") (pintype "unspecified"))
      (node (ref "R-LED43") (pin "1") (pinfunction "1_1") (pintype "unspecified"))
    )
    (net (code "49") (name "Net-(LED44-K)") (class "Default")
      (node (ref "LED44") (pin "1") (pinfunction "K_1") (pintype "unspecified"))
      (node (ref "R-LED44") (pin "1") (pinfunction "1_1") (pintype "unspecified"))
    )
    (net (code "50") (name "Net-(LED45-K)") (class "Default")
      (node (ref "LED45") (pin "1") (pinfunction "K_1") (pintype "unspecified"))
      (node (ref "R-LED45") (pin "1") (pinfunction "1_1") (pintype "unspecified"))
    )
    (net (code "51") (name "Net-(LED46-K)") (class "Default")
      (node (ref "LED46") (pin "1") (pinfunction "K_1") (pintype "unspecified"))
      (node (ref "R-LED46") (pin "1") (pinfunction "1_1") (pintype "unspecified"))
    )
    (net (code "52") (name "Net-(LED47-K)") (class "Default")
      (node (ref "LED47") (pin "1") (pinfunction "K_1") (pintype "unspecified"))
      (node (ref "R-LED47") (pin "1") (pinfunction "1_1") (pintype "unspecified"))
    )
    (net (code "53") (name "Net-(LED48-K)") (class "Default")
      (node (ref "LED48") (pin "1") (pinfunction "K_1") (pintype "unspecified"))
      (node (ref "R-LED48") (pin "1") (pinfunction "1_1") (pintype "unspecified"))
    )
    (net (code "54") (name "R1") (class "Default")
      (node (ref "MUL1") (pin "9") (pinfunction "I0_9") (pintype "unspecified"))
      (node (ref "R1") (pin "2") (pinfunction "2_2") (pintype "input"))
    )
    (net (code "55") (name "R2") (class "Default")
      (node (ref "MUL1") (pin "8") (pinfunction "I1_8") (pintype "unspecified"))
      (node (ref "R2") (pin "2") (pinfunction "2_2") (pintype "input"))
    )
    (net (code "56") (name "R3") (class "Default")
      (node (ref "MUL1") (pin "7") (pinfunction "I2_7") (pintype "unspecified"))
      (node (ref "R3") (pin "2") (pinfunction "2_2") (pintype "input"))
    )
    (net (code "57") (name "R4") (class "Default")
      (node (ref "MUL1") (pin "6") (pinfunction "I3_6") (pintype "unspecified"))
      (node (ref "R4") (pin "2") (pinfunction "2_2") (pintype "input"))
    )
    (net (code "58") (name "R5") (class "Default")
      (node (ref "MUL1") (pin "5") (pinfunction "I4_5") (pintype "unspecified"))
      (node (ref "R5") (pin "2") (pinfunction "2_2") (pintype "input"))
    )
    (net (code "59") (name "R6") (class "Default")
      (node (ref "MUL1") (pin "4") (pinfunction "I5_4") (pintype "unspecified"))
      (node (ref "R6") (pin "2") (pinfunction "2_2") (pintype "input"))
    )
    (net (code "60") (name "R7") (class "Default")
      (node (ref "MUL1") (pin "3") (pinfunction "I6_3") (pintype "unspecified"))
      (node (ref "R7") (pin "2") (pinfunction "2_2") (pintype "input"))
    )
    (net (code "61") (name "R8") (class "Default")
      (node (ref "MUL1") (pin "2") (pinfunction "I7_2") (pintype "unspecified"))
      (node (ref "R8") (pin "2") (pinfunction "2_2") (pintype "input"))
    )
    (net (code "62") (name "R9") (class "Default")
      (node (ref "MUL1") (pin "23") (pinfunction "I8_23") (pintype "unspecified"))
      (node (ref "R9") (pin "2") (pinfunction "2_2") (pintype "input"))
    )
    (net (code "63") (name "R10") (class "Default")
      (node (ref "MUL1") (pin "22") (pinfunction "I9_22") (pintype "unspecified"))
      (node (ref "R10") (pin "2") (pinfunction "2_2") (pintype "input"))
    )
    (net (code "64") (name "R11") (class "Default")
      (node (ref "MUL1") (pin "21") (pinfunction "I10_21") (pintype "unspecified"))
      (node (ref "R11") (pin "2") (pinfunction "2_2") (pintype "input"))
    )
    (net (code "65") (name "R12") (class "Default")
      (node (ref "MUL1") (pin "20") (pinfunction "I11_20") (pintype "unspecified"))
      (node (ref "R12") (pin "2") (pinfunction "2_2") (pintype "input"))
    )
    (net (code "66") (name "R13") (class "Default")
      (node (ref "MUL1") (pin "19") (pinfunction "I12_19") (pintype "unspecified"))
      (node (ref "R13") (pin "2") (pinfunction "2_2") (pintype "input"))
    )
    (net (code "67") (name "R14") (class "Default")
      (node (ref "MUL1") (pin "18") (pinfunction "I13_18") (pintype "unspecified"))
      (node (ref "R14") (pin "2") (pinfunction "2_2") (pintype "input"))
    )
    (net (code "68") (name "R15") (class "Default")
      (node (ref "MUL1") (pin "17") (pinfunction "I14_17") (pintype "unspecified"))
      (node (ref "R15") (pin "2") (pinfunction "2_2") (pintype "input"))
    )
    (net (code "69") (name "R16") (class "Default")
      (node (ref "MUL1") (pin "16") (pinfunction "I15_16") (pintype "unspecified"))
      (node (ref "R16") (pin "2") (pinfunction "2_2") (pintype "input"))
    )
    (net (code "70") (name "R17") (class "Default")
      (node (ref "MUL2") (pin "9") (pinfunction "I0_9") (pintype "unspecified"))
      (node (ref "R17") (pin "2") (pinfunction "2_2") (pintype "input"))
    )
    (net (code "71") (name "R18") (class "Default")
      (node (ref "MUL2") (pin "8") (pinfunction "I1_8") (pintype "unspecified"))
      (node (ref "R18") (pin "2") (pinfunction "2_2") (pintype "input"))
    )
    (net (code "72") (name "R19") (class "Default")
      (node (ref "MUL2") (pin "7") (pinfunction "I2_7") (pintype "unspecified"))
      (node (ref "R19") (pin "2") (pinfunction "2_2") (pintype "input"))
    )
    (net (code "73") (name "R20") (class "Default")
      (node (ref "MUL2") (pin "6") (pinfunction "I3_6") (pintype "unspecified"))
      (node (ref "R20") (pin "2") (pinfunction "2_2") (pintype "input"))
    )
    (net (code "74") (name "R21") (class "Default")
      (node (ref "MUL2") (pin "5") (pinfunction "I4_5") (pintype "unspecified"))
      (node (ref "R21") (pin "2") (pinfunction "2_2") (pintype "input"))
    )
    (net (code "75") (name "R22") (class "Default")
      (node (ref "MUL2") (pin "4") (pinfunction "I5_4") (pintype "unspecified"))
      (node (ref "R22") (pin "2") (pinfunction "2_2") (pintype "input"))
    )
    (net (code "76") (name "R23") (class "Default")
      (node (ref "MUL2") (pin "3") (pinfunction "I6_3") (pintype "unspecified"))
      (node (ref "R23") (pin "2") (pinfunction "2_2") (pintype "input"))
    )
    (net (code "77") (name "R24") (class "Default")
      (node (ref "MUL2") (pin "2") (pinfunction "I7_2") (pintype "unspecified"))
      (node (ref "R24") (pin "2") (pinfunction "2_2") (pintype "input"))
    )
    (net (code "78") (name "R25") (class "Default")
      (node (ref "MUL2") (pin "23") (pinfunction "I8_23") (pintype "unspecified"))
      (node (ref "R25") (pin "2") (pinfunction "2_2") (pintype "input"))
    )
    (net (code "79") (name "R26") (class "Default")
      (node (ref "MUL2") (pin "22") (pinfunction "I9_22") (pintype "unspecified"))
      (node (ref "R26") (pin "2") (pinfunction "2_2") (pintype "input"))
    )
    (net (code "80") (name "R27") (class "Default")
      (node (ref "MUL2") (pin "21") (pinfunction "I10_21") (pintype "unspecified"))
      (node (ref "R27") (pin "2") (pinfunction "2_2") (pintype "input"))
    )
    (net (code "81") (name "R28") (class "Default")
      (node (ref "MUL2") (pin "20") (pinfunction "I11_20") (pintype "unspecified"))
      (node (ref "R28") (pin "2") (pinfunction "2_2") (pintype "input"))
    )
    (net (code "82") (name "R29") (class "Default")
      (node (ref "MUL2") (pin "19") (pinfunction "I12_19") (pintype "unspecified"))
      (node (ref "R29") (pin "2") (pinfunction "2_2") (pintype "input"))
    )
    (net (code "83") (name "R30") (class "Default")
      (node (ref "MUL2") (pin "18") (pinfunction "I13_18") (pintype "unspecified"))
      (node (ref "R30") (pin "2") (pinfunction "2_2") (pintype "input"))
    )
    (net (code "84") (name "R31") (class "Default")
      (node (ref "MUL2") (pin "17") (pinfunction "I14_17") (pintype "unspecified"))
      (node (ref "R31") (pin "2") (pinfunction "2_2") (pintype "input"))
    )
    (net (code "85") (name "R32") (class "Default")
      (node (ref "MUL2") (pin "16") (pinfunction "I15_16") (pintype "unspecified"))
      (node (ref "R32") (pin "2") (pinfunction "2_2") (pintype "input"))
    )
    (net (code "86") (name "R33") (class "Default")
      (node (ref "MUL3") (pin "9") (pinfunction "I0_9") (pintype "unspecified"))
      (node (ref "R33") (pin "2") (pinfunction "2_2") (pintype "input"))
    )
    (net (code "87") (name "R34") (class "Default")
      (node (ref "MUL3") (pin "8") (pinfunction "I1_8") (pintype "unspecified"))
      (node (ref "R34") (pin "2") (pinfunction "2_2") (pintype "input"))
    )
    (net (code "88") (name "R35") (class "Default")
      (node (ref "MUL3") (pin "7") (pinfunction "I2_7") (pintype "unspecified"))
      (node (ref "R35") (pin "2") (pinfunction "2_2") (pintype "input"))
    )
    (net (code "89") (name "R36") (class "Default")
      (node (ref "MUL3") (pin "6") (pinfunction "I3_6") (pintype "unspecified"))
      (node (ref "R36") (pin "2") (pinfunction "2_2") (pintype "input"))
    )
    (net (code "90") (name "R37") (class "Default")
      (node (ref "MUL3") (pin "5") (pinfunction "I4_5") (pintype "unspecified"))
      (node (ref "R37") (pin "2") (pinfunction "2_2") (pintype "input"))
    )
    (net (code "91") (name "R38") (class "Default")
      (node (ref "MUL3") (pin "4") (pinfunction "I5_4") (pintype "unspecified"))
      (node (ref "R38") (pin "2") (pinfunction "2_2") (pintype "input"))
    )
    (net (code "92") (name "R39") (class "Default")
      (node (ref "MUL3") (pin "3") (pinfunction "I6_3") (pintype "unspecified"))
      (node (ref "R39") (pin "2") (pinfunction "2_2") (pintype "input"))
    )
    (net (code "93") (name "R40") (class "Default")
      (node (ref "MUL3") (pin "2") (pinfunction "I7_2") (pintype "unspecified"))
      (node (ref "R40") (pin "2") (pinfunction "2_2") (pintype "input"))
    )
    (net (code "94") (name "R41") (class "Default")
      (node (ref "MUL3") (pin "23") (pinfunction "I8_23") (pintype "unspecified"))
      (node (ref "R41") (pin "2") (pinfunction "2_2") (pintype "input"))
    )
    (net (code "95") (name "R42") (class "Default")
      (node (ref "MUL3") (pin "22") (pinfunction "I9_22") (pintype "unspecified"))
      (node (ref "R42") (pin "2") (pinfunction "2_2") (pintype "input"))
    )
    (net (code "96") (name "R43") (class "Default")
      (node (ref "MUL3") (pin "21") (pinfunction "I10_21") (pintype "unspecified"))
      (node (ref "R43") (pin "2") (pinfunction "2_2") (pintype "input"))
    )
    (net (code "97") (name "R44") (class "Default")
      (node (ref "MUL3") (pin "20") (pinfunction "I11_20") (pintype "unspecified"))
      (node (ref "R44") (pin "2") (pinfunction "2_2") (pintype "input"))
    )
    (net (code "98") (name "R45") (class "Default")
      (node (ref "MUL3") (pin "19") (pinfunction "I12_19") (pintype "unspecified"))
      (node (ref "R45") (pin "2") (pinfunction "2_2") (pintype "input"))
    )
    (net (code "99") (name "R46") (class "Default")
      (node (ref "MUL3") (pin "18") (pinfunction "I13_18") (pintype "unspecified"))
      (node (ref "R46") (pin "2") (pinfunction "2_2") (pintype "input"))
    )
    (net (code "100") (name "R47") (class "Default")
      (node (ref "MUL3") (pin "17") (pinfunction "I14_17") (pintype "unspecified"))
      (node (ref "R47") (pin "2") (pinfunction "2_2") (pintype "input"))
    )
    (net (code "101") (name "R48") (class "Default")
      (node (ref "MUL3") (pin "16") (pinfunction "I15_16") (pintype "unspecified"))
      (node (ref "R48") (pin "2") (pinfunction "2_2") (pintype "input"))
    )
    (net (code "102") (name "RK1") (class "Default")
      (node (ref "MUL1") (pin "15") (pinfunction "E#_15") (pintype "unspecified"))
      (node (ref "R10K4") (pin "2") (pinfunction "2_2") (pintype "unspecified"))
    )
    (net (code "103") (name "RK2") (class "Default")
      (node (ref "MUL2") (pin "15") (pinfunction "E#_15") (pintype "unspecified"))
      (node (ref "R10K5") (pin "2") (pinfunction "2_2") (pintype "unspecified"))
    )
    (net (code "104") (name "RK3") (class "Default")
      (node (ref "MUL3") (pin "15") (pinfunction "E#_15") (pintype "unspecified"))
      (node (ref "R10K6") (pin "2") (pinfunction "2_2") (pintype "unspecified"))
    )
    (net (code "105") (name "S0") (class "Default")
      (node (ref "DI") (pin "1") (pinfunction "1_1") (pintype "unspecified"))
      (node (ref "MUL1") (pin "10") (pinfunction "S0_10") (pintype "unspecified"))
      (node (ref "MUL2") (pin "10") (pinfunction "S0_10") (pintype "unspecified"))
      (node (ref "MUL3") (pin "10") (pinfunction "S0_10") (pintype "unspecified"))
    )
    (net (code "106") (name "S1") (class "Default")
      (node (ref "DI") (pin "2") (pinfunction "2_2") (pintype "unspecified"))
      (node (ref "MUL1") (pin "11") (pinfunction "S1_11") (pintype "unspecified"))
      (node (ref "MUL2") (pin "11") (pinfunction "S1_11") (pintype "unspecified"))
      (node (ref "MUL3") (pin "11") (pinfunction "S1_11") (pintype "unspecified"))
    )
    (net (code "107") (name "S2") (class "Default")
      (node (ref "DI") (pin "3") (pinfunction "3_3") (pintype "unspecified"))
      (node (ref "MUL1") (pin "14") (pinfunction "S2_14") (pintype "unspecified"))
      (node (ref "MUL2") (pin "14") (pinfunction "S2_14") (pintype "unspecified"))
      (node (ref "MUL3") (pin "14") (pinfunction "S2_14") (pintype "unspecified"))
    )
    (net (code "108") (name "S3") (class "Default")
      (node (ref "DI") (pin "4") (pinfunction "4_4") (pintype "unspecified"))
      (node (ref "MUL1") (pin "13") (pinfunction "S3_13") (pintype "unspecified"))
      (node (ref "MUL2") (pin "13") (pinfunction "S3_13") (pintype "unspecified"))
      (node (ref "MUL3") (pin "13") (pinfunction "S3_13") (pintype "unspecified"))
    )
  )
)
